# Sheet1.net
KiCad netlist of a schematic drawn in Altium Designer
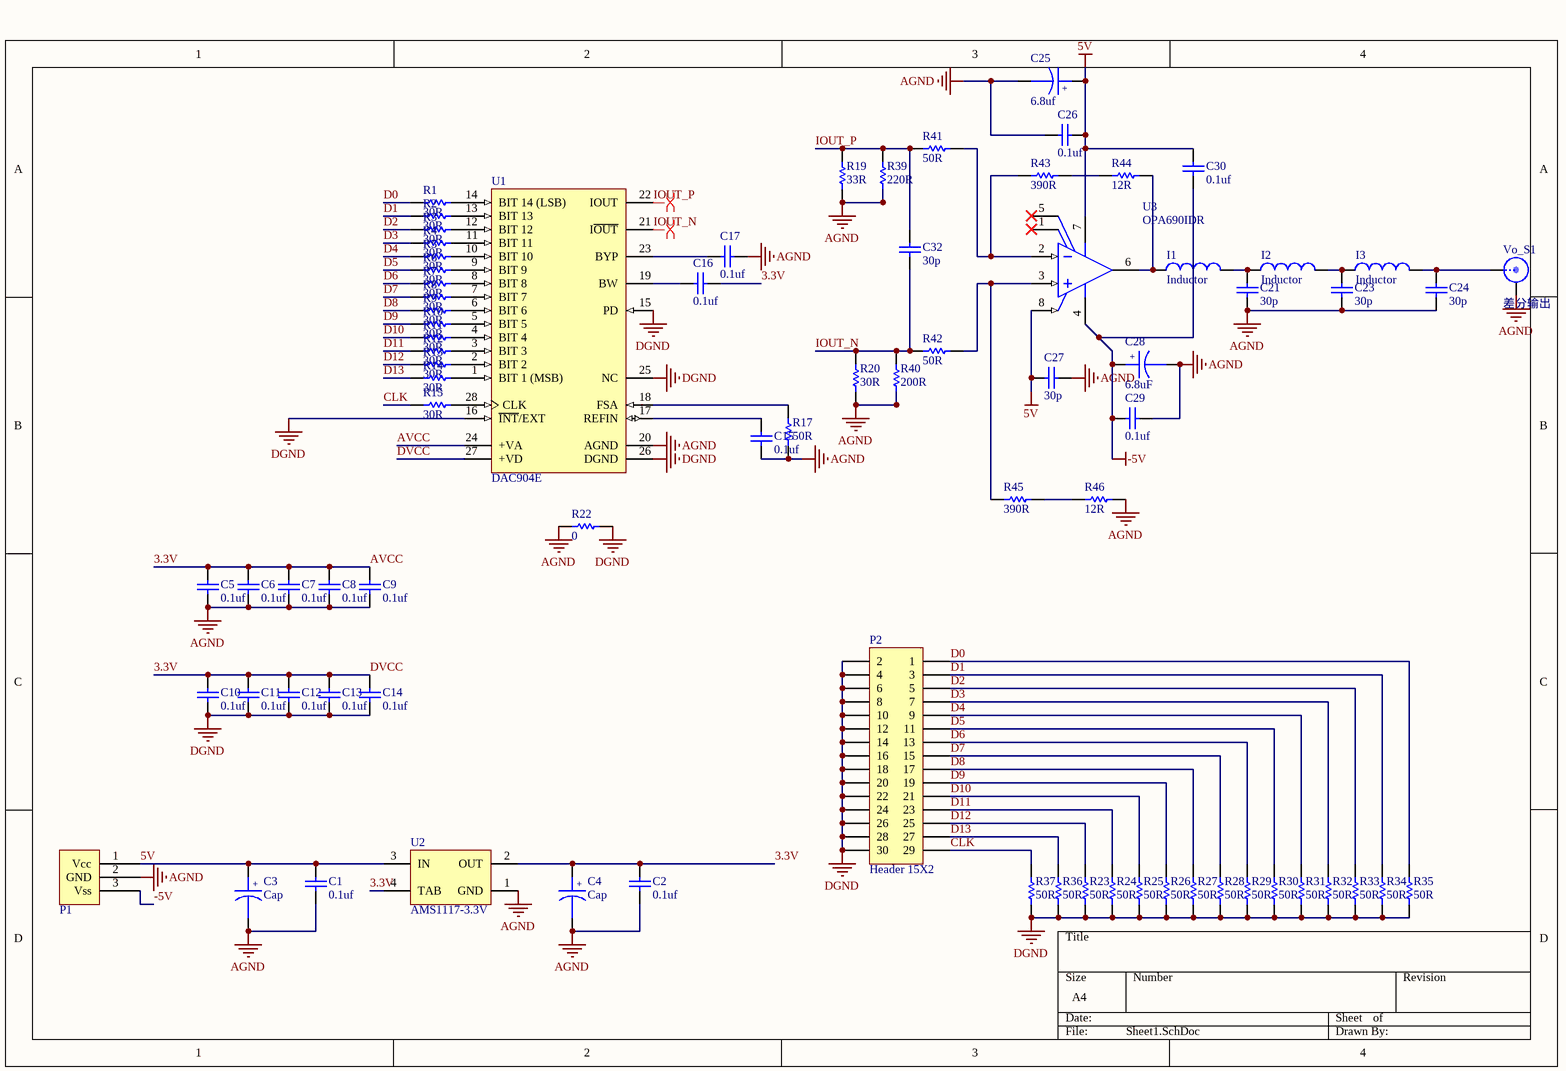
[diagram p0: Sheet1.SchDoc]

(export (version "E")
  (design (tool "Eeschema 10.0.6"))
  (components
    (comp (ref "C1") (value "0.1uf") (footprint "0805") (libsource (lib "Schlib1") (part "Cap")))
    (comp (ref "C2") (value "0.1uf") (footprint "0805") (libsource (lib "Schlib1") (part "Cap")))
    (comp (ref "C3")
      (value "Cap")
      (footprint "7343C-TYPE_D")
      (libsource (lib "Schlib1") (part "Tantalium Cap"))
    )
    (comp (ref "C4")
      (value "Cap")
      (footprint "7343C-TYPE_D")
      (libsource (lib "Schlib1") (part "Tantalium Cap"))
    )
    (comp (ref "C5") (value "0.1uf") (footprint "0603C") (libsource (lib "Schlib1") (part "Cap")))
    (comp (ref "C6") (value "0.1uf") (footprint "0603C") (libsource (lib "Schlib1") (part "Cap")))
    (comp (ref "C7") (value "0.1uf") (footprint "0603C") (libsource (lib "Schlib1") (part "Cap")))
    (comp (ref "C8") (value "0.1uf") (footprint "0603C") (libsource (lib "Schlib1") (part "Cap")))
    (comp (ref "C9") (value "0.1uf") (footprint "0603C") (libsource (lib "Schlib1") (part "Cap")))
    (comp (ref "C10") (value "0.1uf") (footprint "0603C") (libsource (lib "Schlib1") (part "Cap")))
    (comp (ref "C11") (value "0.1uf") (footprint "0603C") (libsource (lib "Schlib1") (part "Cap")))
    (comp (ref "C12") (value "0.1uf") (footprint "0603C") (libsource (lib "Schlib1") (part "Cap")))
    (comp (ref "C13") (value "0.1uf") (footprint "0603C") (libsource (lib "Schlib1") (part "Cap")))
    (comp (ref "C14") (value "0.1uf") (footprint "0603C") (libsource (lib "Schlib1") (part "Cap")))
    (comp (ref "C15") (value "0.1uf") (footprint "0603C") (libsource (lib "Schlib1") (part "Cap")))
    (comp (ref "C16") (value "0.1uf") (footprint "0603C") (libsource (lib "Schlib1") (part "Cap")))
    (comp (ref "C17") (value "0.1uf") (footprint "0603C") (libsource (lib "Schlib1") (part "Cap")))
    (comp (ref "C21") (value "30p") (footprint "0603C") (libsource (lib "Schlib1") (part "Cap")))
    (comp (ref "C23") (value "30p") (footprint "0603C") (libsource (lib "Schlib1") (part "Cap")))
    (comp (ref "C24") (value "30p") (footprint "0603C") (libsource (lib "Schlib1") (part "Cap")))
    (comp (ref "C25")
      (value "6.8uf")
      (footprint "3216C-TYPE_A")
      (libsource (lib "Schlib1") (part "Tantalium Cap"))
    )
    (comp (ref "C26") (value "0.1uf") (footprint "0603C") (libsource (lib "Schlib1") (part "Cap")))
    (comp (ref "C27") (value "30p") (footprint "0603C") (libsource (lib "Schlib1") (part "Cap")))
    (comp (ref "C28")
      (value "6.8uF")
      (footprint "3216C-TYPE_A")
      (libsource (lib "Schlib1") (part "Tantalium Cap"))
    )
    (comp (ref "C29") (value "0.1uf") (footprint "0603C") (libsource (lib "Schlib1") (part "Cap")))
    (comp (ref "C30") (value "0.1uf") (footprint "0603C") (libsource (lib "Schlib1") (part "Cap")))
    (comp (ref "C32") (value "30p") (footprint "0603C") (libsource (lib "Schlib1") (part "Cap")))
    (comp (ref "I1") (value "Inductor") (footprint "0603C") (libsource (lib "Schlib1") (part "Inductor")))
    (comp (ref "I2") (value "Inductor") (footprint "0603C") (libsource (lib "Schlib1") (part "Inductor")))
    (comp (ref "I3") (value "Inductor") (footprint "0603C") (libsource (lib "Schlib1") (part "Inductor")))
    (comp (ref "P1")
      (value "XH2.54-3p")
      (footprint "XH2.54-3p")
      (libsource (lib "Schlib1") (part "XH2.54-3p"))
    )
    (comp (ref "P2")
      (value "Header 15X2")
      (footprint "HDR2X15")
      (description "Header, 15-Pin, Dual row")
      (fields (field (name "PUBLISHER") "Altium Limited"))
      (libsource (lib "Miscellaneous Connectors") (part "Header 15X2"))
    )
    (comp (ref "R1") (value "30R") (footprint "0603R") (libsource (lib "Schlib1") (part "Res")))
    (comp (ref "R2") (value "30R") (footprint "0603R") (libsource (lib "Schlib1") (part "Res")))
    (comp (ref "R3") (value "30R") (footprint "0603R") (libsource (lib "Schlib1") (part "Res")))
    (comp (ref "R4") (value "30R") (footprint "0603R") (libsource (lib "Schlib1") (part "Res")))
    (comp (ref "R5") (value "30R") (footprint "0603R") (libsource (lib "Schlib1") (part "Res")))
    (comp (ref "R6") (value "30R") (footprint "0603R") (libsource (lib "Schlib1") (part "Res")))
    (comp (ref "R7") (value "30R") (footprint "0603R") (libsource (lib "Schlib1") (part "Res")))
    (comp (ref "R8") (value "30R") (footprint "0603R") (libsource (lib "Schlib1") (part "Res")))
    (comp (ref "R9") (value "30R") (footprint "0603R") (libsource (lib "Schlib1") (part "Res")))
    (comp (ref "R10") (value "30R") (footprint "0603R") (libsource (lib "Schlib1") (part "Res")))
    (comp (ref "R11") (value "30R") (footprint "0603R") (libsource (lib "Schlib1") (part "Res")))
    (comp (ref "R12") (value "30R") (footprint "0603R") (libsource (lib "Schlib1") (part "Res")))
    (comp (ref "R13") (value "30R") (footprint "0603R") (libsource (lib "Schlib1") (part "Res")))
    (comp (ref "R14") (value "30R") (footprint "0603R") (libsource (lib "Schlib1") (part "Res")))
    (comp (ref "R15") (value "30R") (footprint "0603R") (libsource (lib "Schlib1") (part "Res")))
    (comp (ref "R17") (value "50R") (footprint "0603R") (libsource (lib "Schlib1") (part "Res")))
    (comp (ref "R19") (value "33R") (footprint "0603R") (libsource (lib "Schlib1") (part "Res")))
    (comp (ref "R20") (value "30R") (footprint "0603R") (libsource (lib "Schlib1") (part "Res")))
    (comp (ref "R22") (value "0") (footprint "0603R") (libsource (lib "Schlib1") (part "Res")))
    (comp (ref "R23") (value "50R") (footprint "0603R") (libsource (lib "Schlib1") (part "Res")))
    (comp (ref "R24") (value "50R") (footprint "0603R") (libsource (lib "Schlib1") (part "Res")))
    (comp (ref "R25") (value "50R") (footprint "0603R") (libsource (lib "Schlib1") (part "Res")))
    (comp (ref "R26") (value "50R") (footprint "0603R") (libsource (lib "Schlib1") (part "Res")))
    (comp (ref "R27") (value "50R") (footprint "0603R") (libsource (lib "Schlib1") (part "Res")))
    (comp (ref "R28") (value "50R") (footprint "0603R") (libsource (lib "Schlib1") (part "Res")))
    (comp (ref "R29") (value "50R") (footprint "0603R") (libsource (lib "Schlib1") (part "Res")))
    (comp (ref "R30") (value "50R") (footprint "0603R") (libsource (lib "Schlib1") (part "Res")))
    (comp (ref "R31") (value "50R") (footprint "0603R") (libsource (lib "Schlib1") (part "Res")))
    (comp (ref "R32") (value "50R") (footprint "0603R") (libsource (lib "Schlib1") (part "Res")))
    (comp (ref "R33") (value "50R") (footprint "0603R") (libsource (lib "Schlib1") (part "Res")))
    (comp (ref "R34") (value "50R") (footprint "0603R") (libsource (lib "Schlib1") (part "Res")))
    (comp (ref "R35") (value "50R") (footprint "0603R") (libsource (lib "Schlib1") (part "Res")))
    (comp (ref "R36") (value "50R") (footprint "0603R") (libsource (lib "Schlib1") (part "Res")))
    (comp (ref "R37") (value "50R") (footprint "0603R") (libsource (lib "Schlib1") (part "Res")))
    (comp (ref "R39") (value "220R") (footprint "0603R") (libsource (lib "Schlib1") (part "Res")))
    (comp (ref "R40") (value "200R") (footprint "0603R") (libsource (lib "Schlib1") (part "Res")))
    (comp (ref "R41") (value "50R") (footprint "0603R") (libsource (lib "Schlib1") (part "Res")))
    (comp (ref "R42") (value "50R") (footprint "0603R") (libsource (lib "Schlib1") (part "Res")))
    (comp (ref "R43") (value "390R") (footprint "0603R") (libsource (lib "Schlib1") (part "Res")))
    (comp (ref "R44") (value "12R") (footprint "0603R") (libsource (lib "Schlib1") (part "Res")))
    (comp (ref "R45") (value "390R") (footprint "0603R") (libsource (lib "Schlib1") (part "Res")))
    (comp (ref "R46") (value "12R") (footprint "0603R") (libsource (lib "Schlib1") (part "Res")))
    (comp (ref "U1")
      (value "DAC904E")
      (footprint "TI-PW28_N")
      (fields (field (name "MANUFACTURER") "Texas Instruments"))
      (libsource (lib "Schlib1") (part "DAC904E"))
    )
    (comp (ref "U2")
      (value "AMS1117-3.3V")
      (footprint "SOT-223")
      (libsource (lib "Schlib1") (part "AMS1117-3.3V"))
    )
    (comp (ref "U3")
      (value "OPA690IDR")
      (footprint "TI-D8_M")
      (fields (field (name "MANUFACTURER") "Texas Instruments"))
      (libsource (lib "Schlib1") (part "OPA690IDR"))
    )
    (comp (ref "Vo_S1") (value "差分输出") (footprint "SMA-LYING") (libsource (lib "Schlib1") (part "SMA")))
  )
  (nets
    (net (code "1") (name "-5V") (class "Default")
      (node (ref "C28") (pin "1") (pinfunction "1_1") (pintype "passive"))
      (node (ref "C29") (pin "1") (pinfunction "1_1") (pintype "passive"))
      (node (ref "C30") (pin "1") (pinfunction "1_1") (pintype "passive"))
      (node (ref "P1") (pin "3") (pinfunction "Vss_3") (pintype "passive"))
      (node (ref "U3") (pin "4") (pinfunction "VS-_4") (pintype "power_in"))
    )
    (net (code "2") (name "/3.3V") (class "Default")
      (node (ref "C10") (pin "2") (pinfunction "2_2") (pintype "passive"))
      (node (ref "C11") (pin "2") (pinfunction "2_2") (pintype "passive"))
      (node (ref "C12") (pin "2") (pinfunction "2_2") (pintype "passive"))
      (node (ref "C13") (pin "2") (pinfunction "2_2") (pintype "passive"))
      (node (ref "C14") (pin "2") (pinfunction "2_2") (pintype "passive"))
      (node (ref "C16") (pin "2") (pinfunction "2_2") (pintype "passive"))
      (node (ref "C2") (pin "2") (pinfunction "2_2") (pintype "passive"))
      (node (ref "C4") (pin "1") (pinfunction "1_1") (pintype "passive"))
      (node (ref "C5") (pin "2") (pinfunction "2_2") (pintype "passive"))
      (node (ref "C6") (pin "2") (pinfunction "2_2") (pintype "passive"))
      (node (ref "C7") (pin "2") (pinfunction "2_2") (pintype "passive"))
      (node (ref "C8") (pin "2") (pinfunction "2_2") (pintype "passive"))
      (node (ref "C9") (pin "2") (pinfunction "2_2") (pintype "passive"))
      (node (ref "U1") (pin "24") (pinfunction "+VA_24") (pintype "power_in"))
      (node (ref "U1") (pin "27") (pinfunction "+VD_27") (pintype "power_in"))
      (node (ref "U2") (pin "2") (pinfunction "OUT_2") (pintype "power_in"))
      (node (ref "U2") (pin "4") (pinfunction "TAB_4") (pintype "power_in"))
    )
    (net (code "3") (name "/CLK") (class "Default")
      (node (ref "P2") (pin "29") (pinfunction "29_29") (pintype "passive"))
      (node (ref "R15") (pin "1") (pinfunction "1_1") (pintype "passive"))
      (node (ref "R37") (pin "2") (pinfunction "2_2") (pintype "passive"))
    )
    (net (code "4") (name "/D0") (class "Default")
      (node (ref "P2") (pin "1") (pinfunction "1_1") (pintype "passive"))
      (node (ref "R1") (pin "1") (pinfunction "1_1") (pintype "passive"))
      (node (ref "R35") (pin "1") (pinfunction "1_1") (pintype "passive"))
    )
    (net (code "5") (name "/D1") (class "Default")
      (node (ref "P2") (pin "3") (pinfunction "3_3") (pintype "passive"))
      (node (ref "R2") (pin "1") (pinfunction "1_1") (pintype "passive"))
      (node (ref "R34") (pin "1") (pinfunction "1_1") (pintype "passive"))
    )
    (net (code "6") (name "/D2") (class "Default")
      (node (ref "P2") (pin "5") (pinfunction "5_5") (pintype "passive"))
      (node (ref "R3") (pin "1") (pinfunction "1_1") (pintype "passive"))
      (node (ref "R33") (pin "1") (pinfunction "1_1") (pintype "passive"))
    )
    (net (code "7") (name "/D3") (class "Default")
      (node (ref "P2") (pin "7") (pinfunction "7_7") (pintype "passive"))
      (node (ref "R32") (pin "1") (pinfunction "1_1") (pintype "passive"))
      (node (ref "R4") (pin "1") (pinfunction "1_1") (pintype "passive"))
    )
    (net (code "8") (name "/D4") (class "Default")
      (node (ref "P2") (pin "9") (pinfunction "9_9") (pintype "passive"))
      (node (ref "R31") (pin "1") (pinfunction "1_1") (pintype "passive"))
      (node (ref "R5") (pin "1") (pinfunction "1_1") (pintype "passive"))
    )
    (net (code "9") (name "/D5") (class "Default")
      (node (ref "P2") (pin "11") (pinfunction "11_11") (pintype "passive"))
      (node (ref "R30") (pin "1") (pinfunction "1_1") (pintype "passive"))
      (node (ref "R6") (pin "1") (pinfunction "1_1") (pintype "passive"))
    )
    (net (code "10") (name "/D6") (class "Default")
      (node (ref "P2") (pin "13") (pinfunction "13_13") (pintype "passive"))
      (node (ref "R29") (pin "1") (pinfunction "1_1") (pintype "passive"))
      (node (ref "R7") (pin "1") (pinfunction "1_1") (pintype "passive"))
    )
    (net (code "11") (name "/D7") (class "Default")
      (node (ref "P2") (pin "15") (pinfunction "15_15") (pintype "passive"))
      (node (ref "R28") (pin "1") (pinfunction "1_1") (pintype "passive"))
      (node (ref "R8") (pin "1") (pinfunction "1_1") (pintype "passive"))
    )
    (net (code "12") (name "/D8") (class "Default")
      (node (ref "P2") (pin "17") (pinfunction "17_17") (pintype "passive"))
      (node (ref "R27") (pin "1") (pinfunction "1_1") (pintype "passive"))
      (node (ref "R9") (pin "1") (pinfunction "1_1") (pintype "passive"))
    )
    (net (code "13") (name "/D9") (class "Default")
      (node (ref "P2") (pin "19") (pinfunction "19_19") (pintype "passive"))
      (node (ref "R10") (pin "1") (pinfunction "1_1") (pintype "passive"))
      (node (ref "R26") (pin "1") (pinfunction "1_1") (pintype "passive"))
    )
    (net (code "14") (name "/D10") (class "Default")
      (node (ref "P2") (pin "21") (pinfunction "21_21") (pintype "passive"))
      (node (ref "R11") (pin "1") (pinfunction "1_1") (pintype "passive"))
      (node (ref "R25") (pin "1") (pinfunction "1_1") (pintype "passive"))
    )
    (net (code "15") (name "/D11") (class "Default")
      (node (ref "P2") (pin "23") (pinfunction "23_23") (pintype "passive"))
      (node (ref "R12") (pin "1") (pinfunction "1_1") (pintype "passive"))
      (node (ref "R24") (pin "1") (pinfunction "1_1") (pintype "passive"))
    )
    (net (code "16") (name "/D12") (class "Default")
      (node (ref "P2") (pin "25") (pinfunction "25_25") (pintype "passive"))
      (node (ref "R13") (pin "1") (pinfunction "1_1") (pintype "passive"))
      (node (ref "R23") (pin "1") (pinfunction "1_1") (pintype "passive"))
    )
    (net (code "17") (name "/D13") (class "Default")
      (node (ref "P2") (pin "27") (pinfunction "27_27") (pintype "passive"))
      (node (ref "R14") (pin "1") (pinfunction "1_1") (pintype "passive"))
      (node (ref "R36") (pin "2") (pinfunction "2_2") (pintype "passive"))
    )
    (net (code "18") (name "/IOUT_N") (class "Default")
      (node (ref "C32") (pin "1") (pinfunction "1_1") (pintype "passive"))
      (node (ref "R20") (pin "2") (pinfunction "2_2") (pintype "passive"))
      (node (ref "R40") (pin "2") (pinfunction "2_2") (pintype "passive"))
      (node (ref "R42") (pin "1") (pinfunction "1_1") (pintype "passive"))
      (node (ref "U1") (pin "21") (pinfunction "I~{OUT}_21") (pintype "tri_state"))
    )
    (net (code "19") (name "/IOUT_P") (class "Default")
      (node (ref "C32") (pin "2") (pinfunction "2_2") (pintype "passive"))
      (node (ref "R19") (pin "2") (pinfunction "2_2") (pintype "passive"))
      (node (ref "R39") (pin "2") (pinfunction "2_2") (pintype "passive"))
      (node (ref "R41") (pin "1") (pinfunction "1_1") (pintype "passive"))
      (node (ref "U1") (pin "22") (pinfunction "IOUT_22") (pintype "tri_state"))
    )
    (net (code "20") (name "5V") (class "Default")
      (node (ref "C1") (pin "2") (pinfunction "2_2") (pintype "passive"))
      (node (ref "C25") (pin "1") (pinfunction "1_1") (pintype "passive"))
      (node (ref "C26") (pin "1") (pinfunction "1_1") (pintype "passive"))
      (node (ref "C27") (pin "1") (pinfunction "1_1") (pintype "passive"))
      (node (ref "C3") (pin "1") (pinfunction "1_1") (pintype "passive"))
      (node (ref "C30") (pin "2") (pinfunction "2_2") (pintype "passive"))
      (node (ref "P1") (pin "1") (pinfunction "Vcc_1") (pintype "passive"))
      (node (ref "U2") (pin "3") (pinfunction "IN_3") (pintype "power_in"))
      (node (ref "U3") (pin "7") (pinfunction "VS+_7") (pintype "power_in"))
      (node (ref "U3") (pin "8") (pinfunction "~{DIS}_8") (pintype "input"))
    )
    (net (code "21") (name "AGND") (class "Default")
      (node (ref "C1") (pin "1") (pinfunction "1_1") (pintype "passive"))
      (node (ref "C15") (pin "1") (pinfunction "1_1") (pintype "passive"))
      (node (ref "C17") (pin "2") (pinfunction "2_2") (pintype "passive"))
      (node (ref "C2") (pin "1") (pinfunction "1_1") (pintype "passive"))
      (node (ref "C21") (pin "2") (pinfunction "2_2") (pintype "passive"))
      (node (ref "C23") (pin "1") (pinfunction "1_1") (pintype "passive"))
      (node (ref "C24") (pin "1") (pinfunction "1_1") (pintype "passive"))
      (node (ref "C25") (pin "2") (pinfunction "2_2") (pintype "passive"))
      (node (ref "C26") (pin "2") (pinfunction "2_2") (pintype "passive"))
      (node (ref "C27") (pin "2") (pinfunction "2_2") (pintype "passive"))
      (node (ref "C28") (pin "2") (pinfunction "2_2") (pintype "passive"))
      (node (ref "C29") (pin "2") (pinfunction "2_2") (pintype "passive"))
      (node (ref "C3") (pin "2") (pinfunction "2_2") (pintype "passive"))
      (node (ref "C4") (pin "2") (pinfunction "2_2") (pintype "passive"))
      (node (ref "C5") (pin "1") (pinfunction "1_1") (pintype "passive"))
      (node (ref "C6") (pin "1") (pinfunction "1_1") (pintype "passive"))
      (node (ref "C7") (pin "1") (pinfunction "1_1") (pintype "passive"))
      (node (ref "C8") (pin "1") (pinfunction "1_1") (pintype "passive"))
      (node (ref "C9") (pin "1") (pinfunction "1_1") (pintype "passive"))
      (node (ref "P1") (pin "2") (pinfunction "GND_2") (pintype "passive"))
      (node (ref "R17") (pin "1") (pinfunction "1_1") (pintype "passive"))
      (node (ref "R19") (pin "1") (pinfunction "1_1") (pintype "passive"))
      (node (ref "R20") (pin "1") (pinfunction "1_1") (pintype "passive"))
      (node (ref "R22") (pin "1") (pinfunction "1_1") (pintype "passive"))
      (node (ref "R39") (pin "1") (pinfunction "1_1") (pintype "passive"))
      (node (ref "R40") (pin "1") (pinfunction "1_1") (pintype "passive"))
      (node (ref "R46") (pin "2") (pinfunction "2_2") (pintype "passive"))
      (node (ref "U1") (pin "20") (pinfunction "AGND_20") (pintype "power_in"))
      (node (ref "U2") (pin "1") (pinfunction "GND_1") (pintype "power_in"))
      (node (ref "Vo_S1") (pin "1") (pinfunction "1_1") (pintype "passive"))
    )
    (net (code "22") (name "DGND") (class "Default")
      (node (ref "C10") (pin "1") (pinfunction "1_1") (pintype "passive"))
      (node (ref "C11") (pin "1") (pinfunction "1_1") (pintype "passive"))
      (node (ref "C12") (pin "1") (pinfunction "1_1") (pintype "passive"))
      (node (ref "C13") (pin "1") (pinfunction "1_1") (pintype "passive"))
      (node (ref "C14") (pin "1") (pinfunction "1_1") (pintype "passive"))
      (node (ref "P2") (pin "10") (pinfunction "10_10") (pintype "passive"))
      (node (ref "P2") (pin "12") (pinfunction "12_12") (pintype "passive"))
      (node (ref "P2") (pin "14") (pinfunction "14_14") (pintype "passive"))
      (node (ref "P2") (pin "16") (pinfunction "16_16") (pintype "passive"))
      (node (ref "P2") (pin "18") (pinfunction "18_18") (pintype "passive"))
      (node (ref "P2") (pin "2") (pinfunction "2_2") (pintype "passive"))
      (node (ref "P2") (pin "20") (pinfunction "20_20") (pintype "passive"))
      (node (ref "P2") (pin "22") (pinfunction "22_22") (pintype "passive"))
      (node (ref "P2") (pin "24") (pinfunction "24_24") (pintype "passive"))
      (node (ref "P2") (pin "26") (pinfunction "26_26") (pintype "passive"))
      (node (ref "P2") (pin "28") (pinfunction "28_28") (pintype "passive"))
      (node (ref "P2") (pin "30") (pinfunction "30_30") (pintype "passive"))
      (node (ref "P2") (pin "4") (pinfunction "4_4") (pintype "passive"))
      (node (ref "P2") (pin "6") (pinfunction "6_6") (pintype "passive"))
      (node (ref "P2") (pin "8") (pinfunction "8_8") (pintype "passive"))
      (node (ref "R22") (pin "2") (pinfunction "2_2") (pintype "passive"))
      (node (ref "R23") (pin "2") (pinfunction "2_2") (pintype "passive"))
      (node (ref "R24") (pin "2") (pinfunction "2_2") (pintype "passive"))
      (node (ref "R25") (pin "2") (pinfunction "2_2") (pintype "passive"))
      (node (ref "R26") (pin "2") (pinfunction "2_2") (pintype "passive"))
      (node (ref "R27") (pin "2") (pinfunction "2_2") (pintype "passive"))
      (node (ref "R28") (pin "2") (pinfunction "2_2") (pintype "passive"))
      (node (ref "R29") (pin "2") (pinfunction "2_2") (pintype "passive"))
      (node (ref "R30") (pin "2") (pinfunction "2_2") (pintype "passive"))
      (node (ref "R31") (pin "2") (pinfunction "2_2") (pintype "passive"))
      (node (ref "R32") (pin "2") (pinfunction "2_2") (pintype "passive"))
      (node (ref "R33") (pin "2") (pinfunction "2_2") (pintype "passive"))
      (node (ref "R34") (pin "2") (pinfunction "2_2") (pintype "passive"))
      (node (ref "R35") (pin "2") (pinfunction "2_2") (pintype "passive"))
      (node (ref "R36") (pin "1") (pinfunction "1_1") (pintype "passive"))
      (node (ref "R37") (pin "1") (pinfunction "1_1") (pintype "passive"))
      (node (ref "U1") (pin "15") (pinfunction "PD_15") (pintype "input"))
      (node (ref "U1") (pin "16") (pinfunction "~{INT}/EXT_16") (pintype "input"))
      (node (ref "U1") (pin "25") (pinfunction "NC_25") (pintype "passive"))
      (node (ref "U1") (pin "26") (pinfunction "DGND_26") (pintype "power_in"))
    )
    (net (code "23") (name "Net-(C21-Pad1)") (class "Default")
      (node (ref "C21") (pin "1") (pinfunction "1_1") (pintype "passive"))
      (node (ref "I1") (pin "2") (pinfunction "2_2") (pintype "passive"))
      (node (ref "I2") (pin "1") (pinfunction "1_1") (pintype "passive"))
    )
    (net (code "24") (name "Net-(C23-Pad2)") (class "Default")
      (node (ref "C23") (pin "2") (pinfunction "2_2") (pintype "passive"))
      (node (ref "I2") (pin "2") (pinfunction "2_2") (pintype "passive"))
      (node (ref "I3") (pin "1") (pinfunction "1_1") (pintype "passive"))
    )
    (net (code "25") (name "Net-(C24-Pad2)") (class "Default")
      (node (ref "C24") (pin "2") (pinfunction "2_2") (pintype "passive"))
      (node (ref "I3") (pin "2") (pinfunction "2_2") (pintype "passive"))
      (node (ref "Vo_S1") (pin "0") (pinfunction "0_0") (pintype "passive"))
    )
    (net (code "26") (name "Net-(R43-Pad2)") (class "Default")
      (node (ref "R43") (pin "2") (pinfunction "2_2") (pintype "passive"))
      (node (ref "R44") (pin "1") (pinfunction "1_1") (pintype "passive"))
    )
    (net (code "27") (name "Net-(R45-Pad2)") (class "Default")
      (node (ref "R45") (pin "2") (pinfunction "2_2") (pintype "passive"))
      (node (ref "R46") (pin "1") (pinfunction "1_1") (pintype "passive"))
    )
    (net (code "28") (name "Net-(U1-BIT_1_(MSB))") (class "Default")
      (node (ref "R14") (pin "2") (pinfunction "2_2") (pintype "passive"))
      (node (ref "U1") (pin "1") (pinfunction "BIT_1_(MSB)_1") (pintype "input"))
    )
    (net (code "29") (name "Net-(U1-BIT_2)") (class "Default")
      (node (ref "R13") (pin "2") (pinfunction "2_2") (pintype "passive"))
      (node (ref "U1") (pin "2") (pinfunction "BIT_2_2") (pintype "input"))
    )
    (net (code "30") (name "Net-(U1-BIT_3)") (class "Default")
      (node (ref "R12") (pin "2") (pinfunction "2_2") (pintype "passive"))
      (node (ref "U1") (pin "3") (pinfunction "BIT_3_3") (pintype "input"))
    )
    (net (code "31") (name "Net-(U1-BIT_4)") (class "Default")
      (node (ref "R11") (pin "2") (pinfunction "2_2") (pintype "passive"))
      (node (ref "U1") (pin "4") (pinfunction "BIT_4_4") (pintype "input"))
    )
    (net (code "32") (name "Net-(U1-BIT_5)") (class "Default")
      (node (ref "R10") (pin "2") (pinfunction "2_2") (pintype "passive"))
      (node (ref "U1") (pin "5") (pinfunction "BIT_5_5") (pintype "input"))
    )
    (net (code "33") (name "Net-(U1-BIT_6)") (class "Default")
      (node (ref "R9") (pin "2") (pinfunction "2_2") (pintype "passive"))
      (node (ref "U1") (pin "6") (pinfunction "BIT_6_6") (pintype "input"))
    )
    (net (code "34") (name "Net-(U1-BIT_7)") (class "Default")
      (node (ref "R8") (pin "2") (pinfunction "2_2") (pintype "passive"))
      (node (ref "U1") (pin "7") (pinfunction "BIT_7_7") (pintype "input"))
    )
    (net (code "35") (name "Net-(U1-BIT_8)") (class "Default")
      (node (ref "R7") (pin "2") (pinfunction "2_2") (pintype "passive"))
      (node (ref "U1") (pin "8") (pinfunction "BIT_8_8") (pintype "input"))
    )
    (net (code "36") (name "Net-(U1-BIT_9)") (class "Default")
      (node (ref "R6") (pin "2") (pinfunction "2_2") (pintype "passive"))
      (node (ref "U1") (pin "9") (pinfunction "BIT_9_9") (pintype "input"))
    )
    (net (code "37") (name "Net-(U1-BIT_10)") (class "Default")
      (node (ref "R5") (pin "2") (pinfunction "2_2") (pintype "passive"))
      (node (ref "U1") (pin "10") (pinfunction "BIT_10_10") (pintype "input"))
    )
    (net (code "38") (name "Net-(U1-BIT_11)") (class "Default")
      (node (ref "R4") (pin "2") (pinfunction "2_2") (pintype "passive"))
      (node (ref "U1") (pin "11") (pinfunction "BIT_11_11") (pintype "input"))
    )
    (net (code "39") (name "Net-(U1-BIT_12)") (class "Default")
      (node (ref "R3") (pin "2") (pinfunction "2_2") (pintype "passive"))
      (node (ref "U1") (pin "12") (pinfunction "BIT_12_12") (pintype "input"))
    )
    (net (code "40") (name "Net-(U1-BIT_13)") (class "Default")
      (node (ref "R2") (pin "2") (pinfunction "2_2") (pintype "passive"))
      (node (ref "U1") (pin "13") (pinfunction "BIT_13_13") (pintype "input"))
    )
    (net (code "41") (name "Net-(U1-BIT_14_(LSB))") (class "Default")
      (node (ref "R1") (pin "2") (pinfunction "2_2") (pintype "passive"))
      (node (ref "U1") (pin "14") (pinfunction "BIT_14_(LSB)_14") (pintype "input"))
    )
    (net (code "42") (name "Net-(U1-BW)") (class "Default")
      (node (ref "C16") (pin "1") (pinfunction "1_1") (pintype "passive"))
      (node (ref "U1") (pin "19") (pinfunction "BW_19") (pintype "passive"))
    )
    (net (code "43") (name "Net-(U1-BYP)") (class "Default")
      (node (ref "C17") (pin "1") (pinfunction "1_1") (pintype "passive"))
      (node (ref "U1") (pin "23") (pinfunction "BYP_23") (pintype "passive"))
    )
    (net (code "44") (name "Net-(U1-CLK)") (class "Default")
      (node (ref "R15") (pin "2") (pinfunction "2_2") (pintype "passive"))
      (node (ref "U1") (pin "28") (pinfunction "CLK_28") (pintype "input"))
    )
    (net (code "45") (name "Net-(U1-FSA)") (class "Default")
      (node (ref "R17") (pin "2") (pinfunction "2_2") (pintype "passive"))
      (node (ref "U1") (pin "18") (pinfunction "FSA_18") (pintype "input"))
    )
    (net (code "46") (name "Net-(U1-REFIN)") (class "Default")
      (node (ref "C15") (pin "2") (pinfunction "2_2") (pintype "passive"))
      (node (ref "U1") (pin "17") (pinfunction "REFIN_17") (pintype "bidirectional"))
    )
    (net (code "47") (name "Net-(U3-IN+)") (class "Default")
      (node (ref "R42") (pin "2") (pinfunction "2_2") (pintype "passive"))
      (node (ref "R45") (pin "1") (pinfunction "1_1") (pintype "passive"))
      (node (ref "U3") (pin "3") (pinfunction "IN+_3") (pintype "input"))
    )
    (net (code "48") (name "Net-(U3-IN-)") (class "Default")
      (node (ref "R41") (pin "2") (pinfunction "2_2") (pintype "passive"))
      (node (ref "R43") (pin "1") (pinfunction "1_1") (pintype "passive"))
      (node (ref "U3") (pin "2") (pinfunction "IN-_2") (pintype "input"))
    )
    (net (code "49") (name "Net-(U3-OUT)") (class "Default")
      (node (ref "I1") (pin "1") (pinfunction "1_1") (pintype "passive"))
      (node (ref "R44") (pin "2") (pinfunction "2_2") (pintype "passive"))
      (node (ref "U3") (pin "6") (pinfunction "OUT_6") (pintype "tri_state"))
    )
    (net (code "50") (name "unconnected-(U3-NC-Pad1)") (class "Default")
      (node (ref "U3") (pin "1") (pinfunction "NC_1") (pintype "passive+no_connect"))
    )
    (net (code "51") (name "unconnected-(U3-NC-Pad5)") (class "Default")
      (node (ref "U3") (pin "5") (pinfunction "NC_5") (pintype "passive+no_connect"))
    )
  )
)
